# unicorder-mk-1_4-display.net
KiCad netlist of a schematic drawn in EAGLE
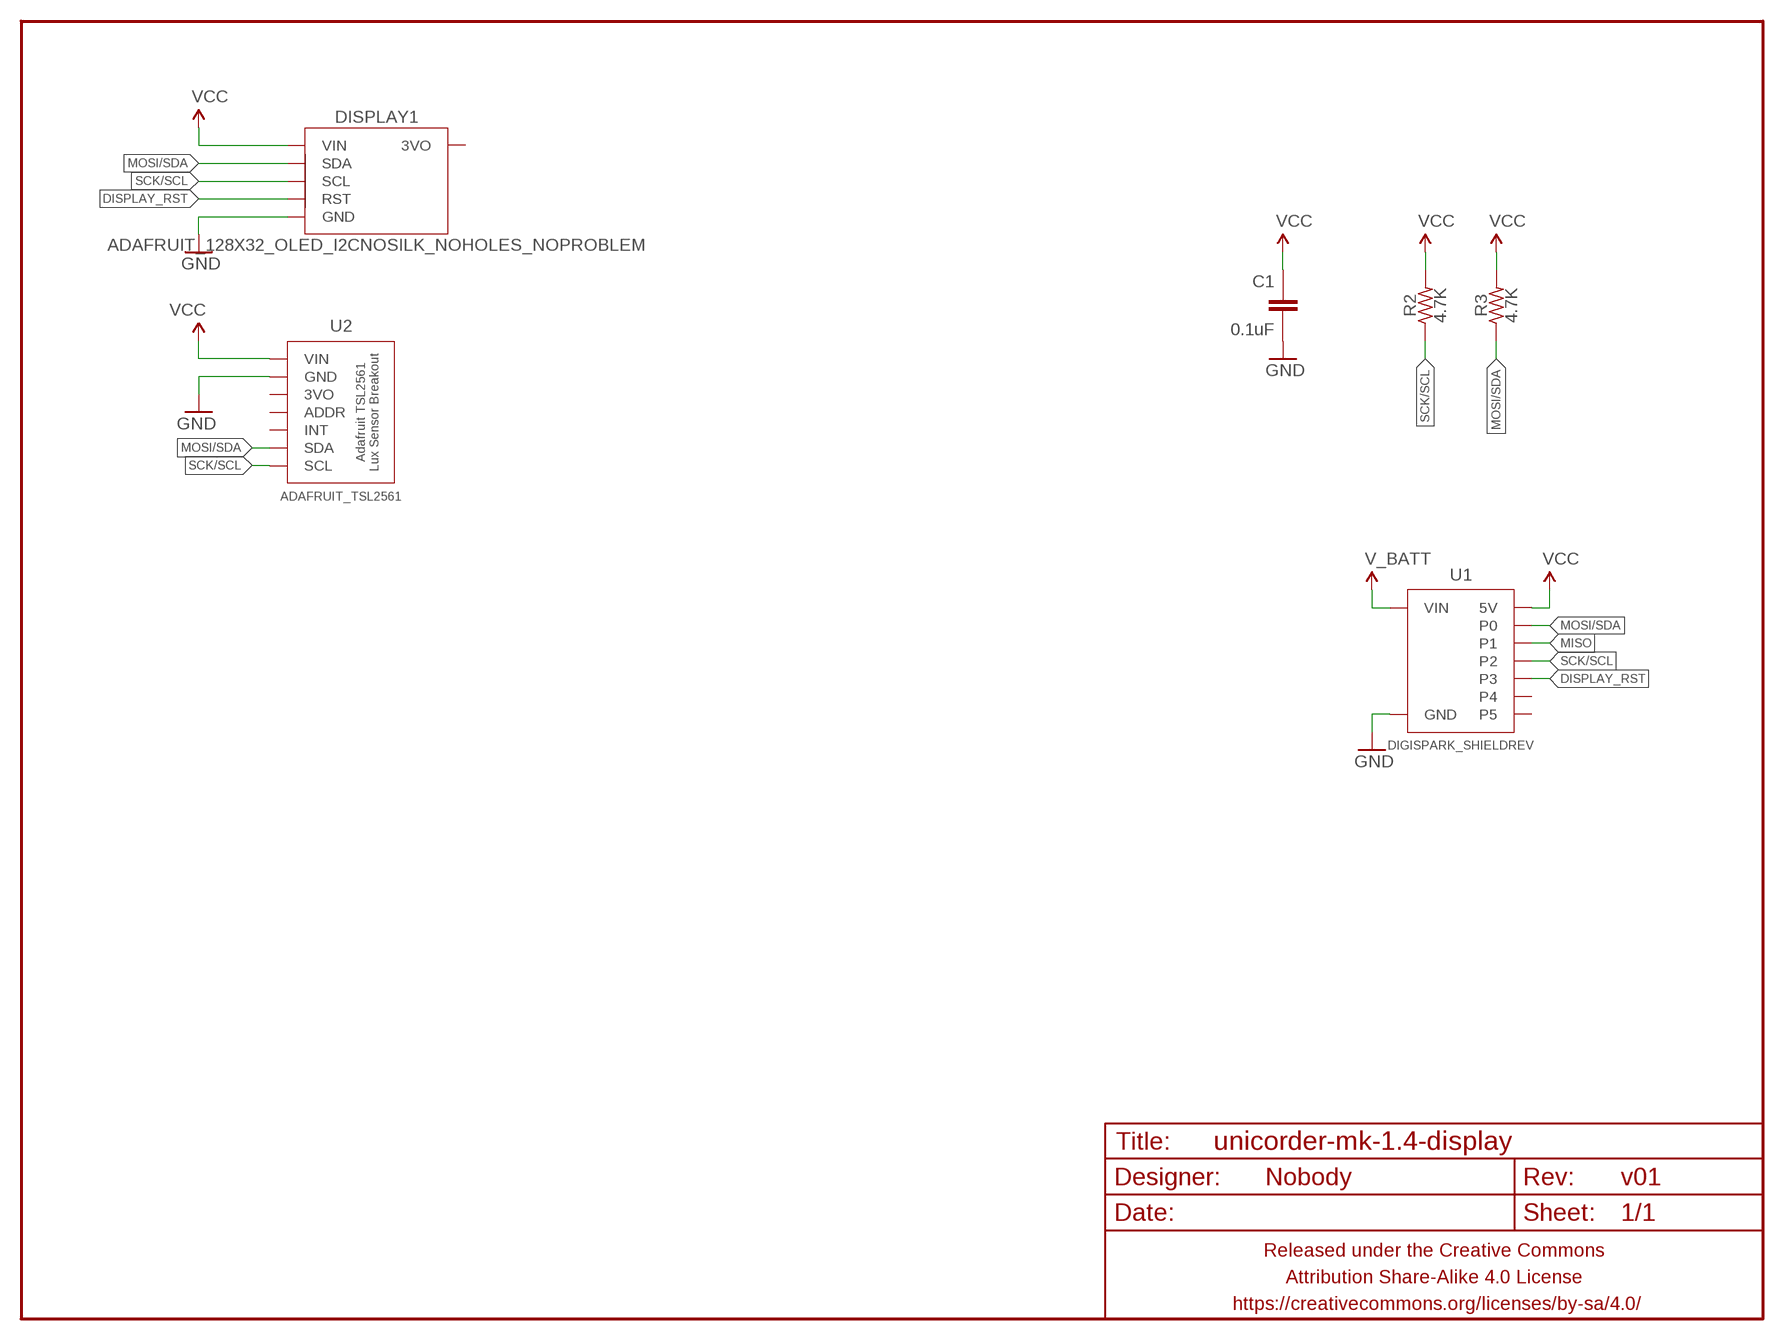
[diagram p0: schematic, sheet 1]

(export (version "E")
  (design (tool "Eeschema 10.0.6"))
  (components
    (comp (ref "C1")
      (value "0.1uF")
      (footprint "eagle-import:C025-024X044")
      (libsource (lib "eagle-import") (part "CAPACITOR-CERAMIC025-024X044"))
    )
    (comp (ref "DISPLAY1")
      (value "ADAFRUIT_128X32_OLED_I2CNOSILK_NOHOLES_NOPROBLEM")
      (footprint "eagle-import:ADAFRUIT_128X32_OLED_I2C_CLOSER_NS")
      (libsource (lib "eagle-import") (part "ADAFRUIT_128X32_OLED_I2CNOSILK_NOHOLES_NOPROBLEM"))
    )
    (comp (ref "FRAME1")
      (value "FRAME-LETTERNO_PACKAGE")
      (footprint "eagle-import:DUMMY")
      (fields (field (name "DESIGNER") "Nobody"))
      (libsource (lib "eagle-import") (part "FRAME-LETTERNO_PACKAGE"))
    )
    (comp (ref "R2")
      (value "4.7K")
      (footprint "eagle-import:RESISTOR-AXIAL-PTH-7.62MM")
      (libsource (lib "eagle-import") (part "RESISTORPTH-AXIAL-7.62MM"))
    )
    (comp (ref "R3")
      (value "4.7K")
      (footprint "eagle-import:RESISTOR-AXIAL-PTH-7.62MM")
      (libsource (lib "eagle-import") (part "RESISTORPTH-AXIAL-7.62MM"))
    )
    (comp (ref "U1")
      (value "DIGISPARK_SHIELDREV")
      (footprint "eagle-import:DIGISPARK_SHIELD_REV")
      (libsource (lib "eagle-import") (part "DIGISPARK_SHIELDREV"))
    )
    (comp (ref "U2")
      (value "ADAFRUIT_TSL2561")
      (footprint "eagle-import:ADAFRUIT_TSL2561")
      (libsource (lib "eagle-import") (part "ADAFRUIT_TSL2561"))
    )
  )
  (nets
    (net (code "1") (name "DISPLAY_RST") (class "Default")
      (node (ref "DISPLAY1") (pin "RST") (pinfunction "RST_RST") (pintype "bidirectional"))
      (node (ref "U1") (pin "P3") (pinfunction "P3_P3") (pintype "bidirectional"))
    )
    (net (code "2") (name "GND") (class "Default")
      (node (ref "C1") (pin "2") (pinfunction "2_2") (pintype "passive"))
      (node (ref "DISPLAY1") (pin "GND") (pinfunction "GND_GND") (pintype "bidirectional"))
      (node (ref "U1") (pin "GND") (pinfunction "GND_GND") (pintype "bidirectional"))
      (node (ref "U2") (pin "GND") (pinfunction "GND_GND") (pintype "bidirectional"))
    )
    (net (code "3") (name "MISO") (class "Default")
      (node (ref "U1") (pin "P1") (pinfunction "P1_P1") (pintype "bidirectional"))
    )
    (net (code "4") (name "MOSI{slash}SDA") (class "Default")
      (node (ref "DISPLAY1") (pin "SDA") (pinfunction "SDA_SDA") (pintype "bidirectional"))
      (node (ref "R3") (pin "P$1") (pinfunction "1_P$1") (pintype "passive"))
      (node (ref "U1") (pin "P0") (pinfunction "P0_P0") (pintype "bidirectional"))
      (node (ref "U2") (pin "SDA") (pinfunction "SDA_SDA") (pintype "bidirectional"))
    )
    (net (code "5") (name "SCK{slash}SCL") (class "Default")
      (node (ref "DISPLAY1") (pin "SCL") (pinfunction "SCL_SCL") (pintype "bidirectional"))
      (node (ref "R2") (pin "P$1") (pinfunction "1_P$1") (pintype "passive"))
      (node (ref "U1") (pin "P2") (pinfunction "P2_P2") (pintype "bidirectional"))
      (node (ref "U2") (pin "SCL") (pinfunction "SCL_SCL") (pintype "bidirectional"))
    )
    (net (code "6") (name "VCC") (class "Default")
      (node (ref "C1") (pin "1") (pinfunction "1_1") (pintype "passive"))
      (node (ref "DISPLAY1") (pin "VIN") (pinfunction "VIN_VIN") (pintype "bidirectional"))
      (node (ref "R2") (pin "P$2") (pinfunction "2_P$2") (pintype "passive"))
      (node (ref "R3") (pin "P$2") (pinfunction "2_P$2") (pintype "passive"))
      (node (ref "U1") (pin "5V") (pinfunction "5V_5V") (pintype "bidirectional"))
      (node (ref "U2") (pin "VIN") (pinfunction "VIN_VIN") (pintype "bidirectional"))
    )
    (net (code "7") (name "V_BATT") (class "Default")
      (node (ref "U1") (pin "VIN") (pinfunction "VIN_VIN") (pintype "bidirectional"))
    )
    (net (code "8") (name "unconnected-(DISPLAY1-Pad3VO)") (class "Default")
      (node (ref "DISPLAY1") (pin "3VO") (pinfunction "3VO_3VO") (pintype "bidirectional"))
    )
    (net (code "9") (name "unconnected-(U1-PadP4)") (class "Default")
      (node (ref "U1") (pin "P4") (pinfunction "P4_P4") (pintype "bidirectional"))
    )
    (net (code "10") (name "unconnected-(U1-PadP5)") (class "Default")
      (node (ref "U1") (pin "P5") (pinfunction "P5_P5") (pintype "bidirectional"))
    )
    (net (code "11") (name "unconnected-(U2-Pad3VO)") (class "Default")
      (node (ref "U2") (pin "3VO") (pinfunction "3VO_3VO") (pintype "bidirectional"))
    )
    (net (code "12") (name "unconnected-(U2-PadADDR)") (class "Default")
      (node (ref "U2") (pin "ADDR") (pinfunction "ADDR_ADDR") (pintype "bidirectional"))
    )
    (net (code "13") (name "unconnected-(U2-PadINT)") (class "Default")
      (node (ref "U2") (pin "INT") (pinfunction "INT_INT") (pintype "bidirectional"))
    )
  )
)
